# 1-Schematic_Indoor_WiFi_temperature_sens.net
KiCad netlist of a schematic drawn in EasyEDA
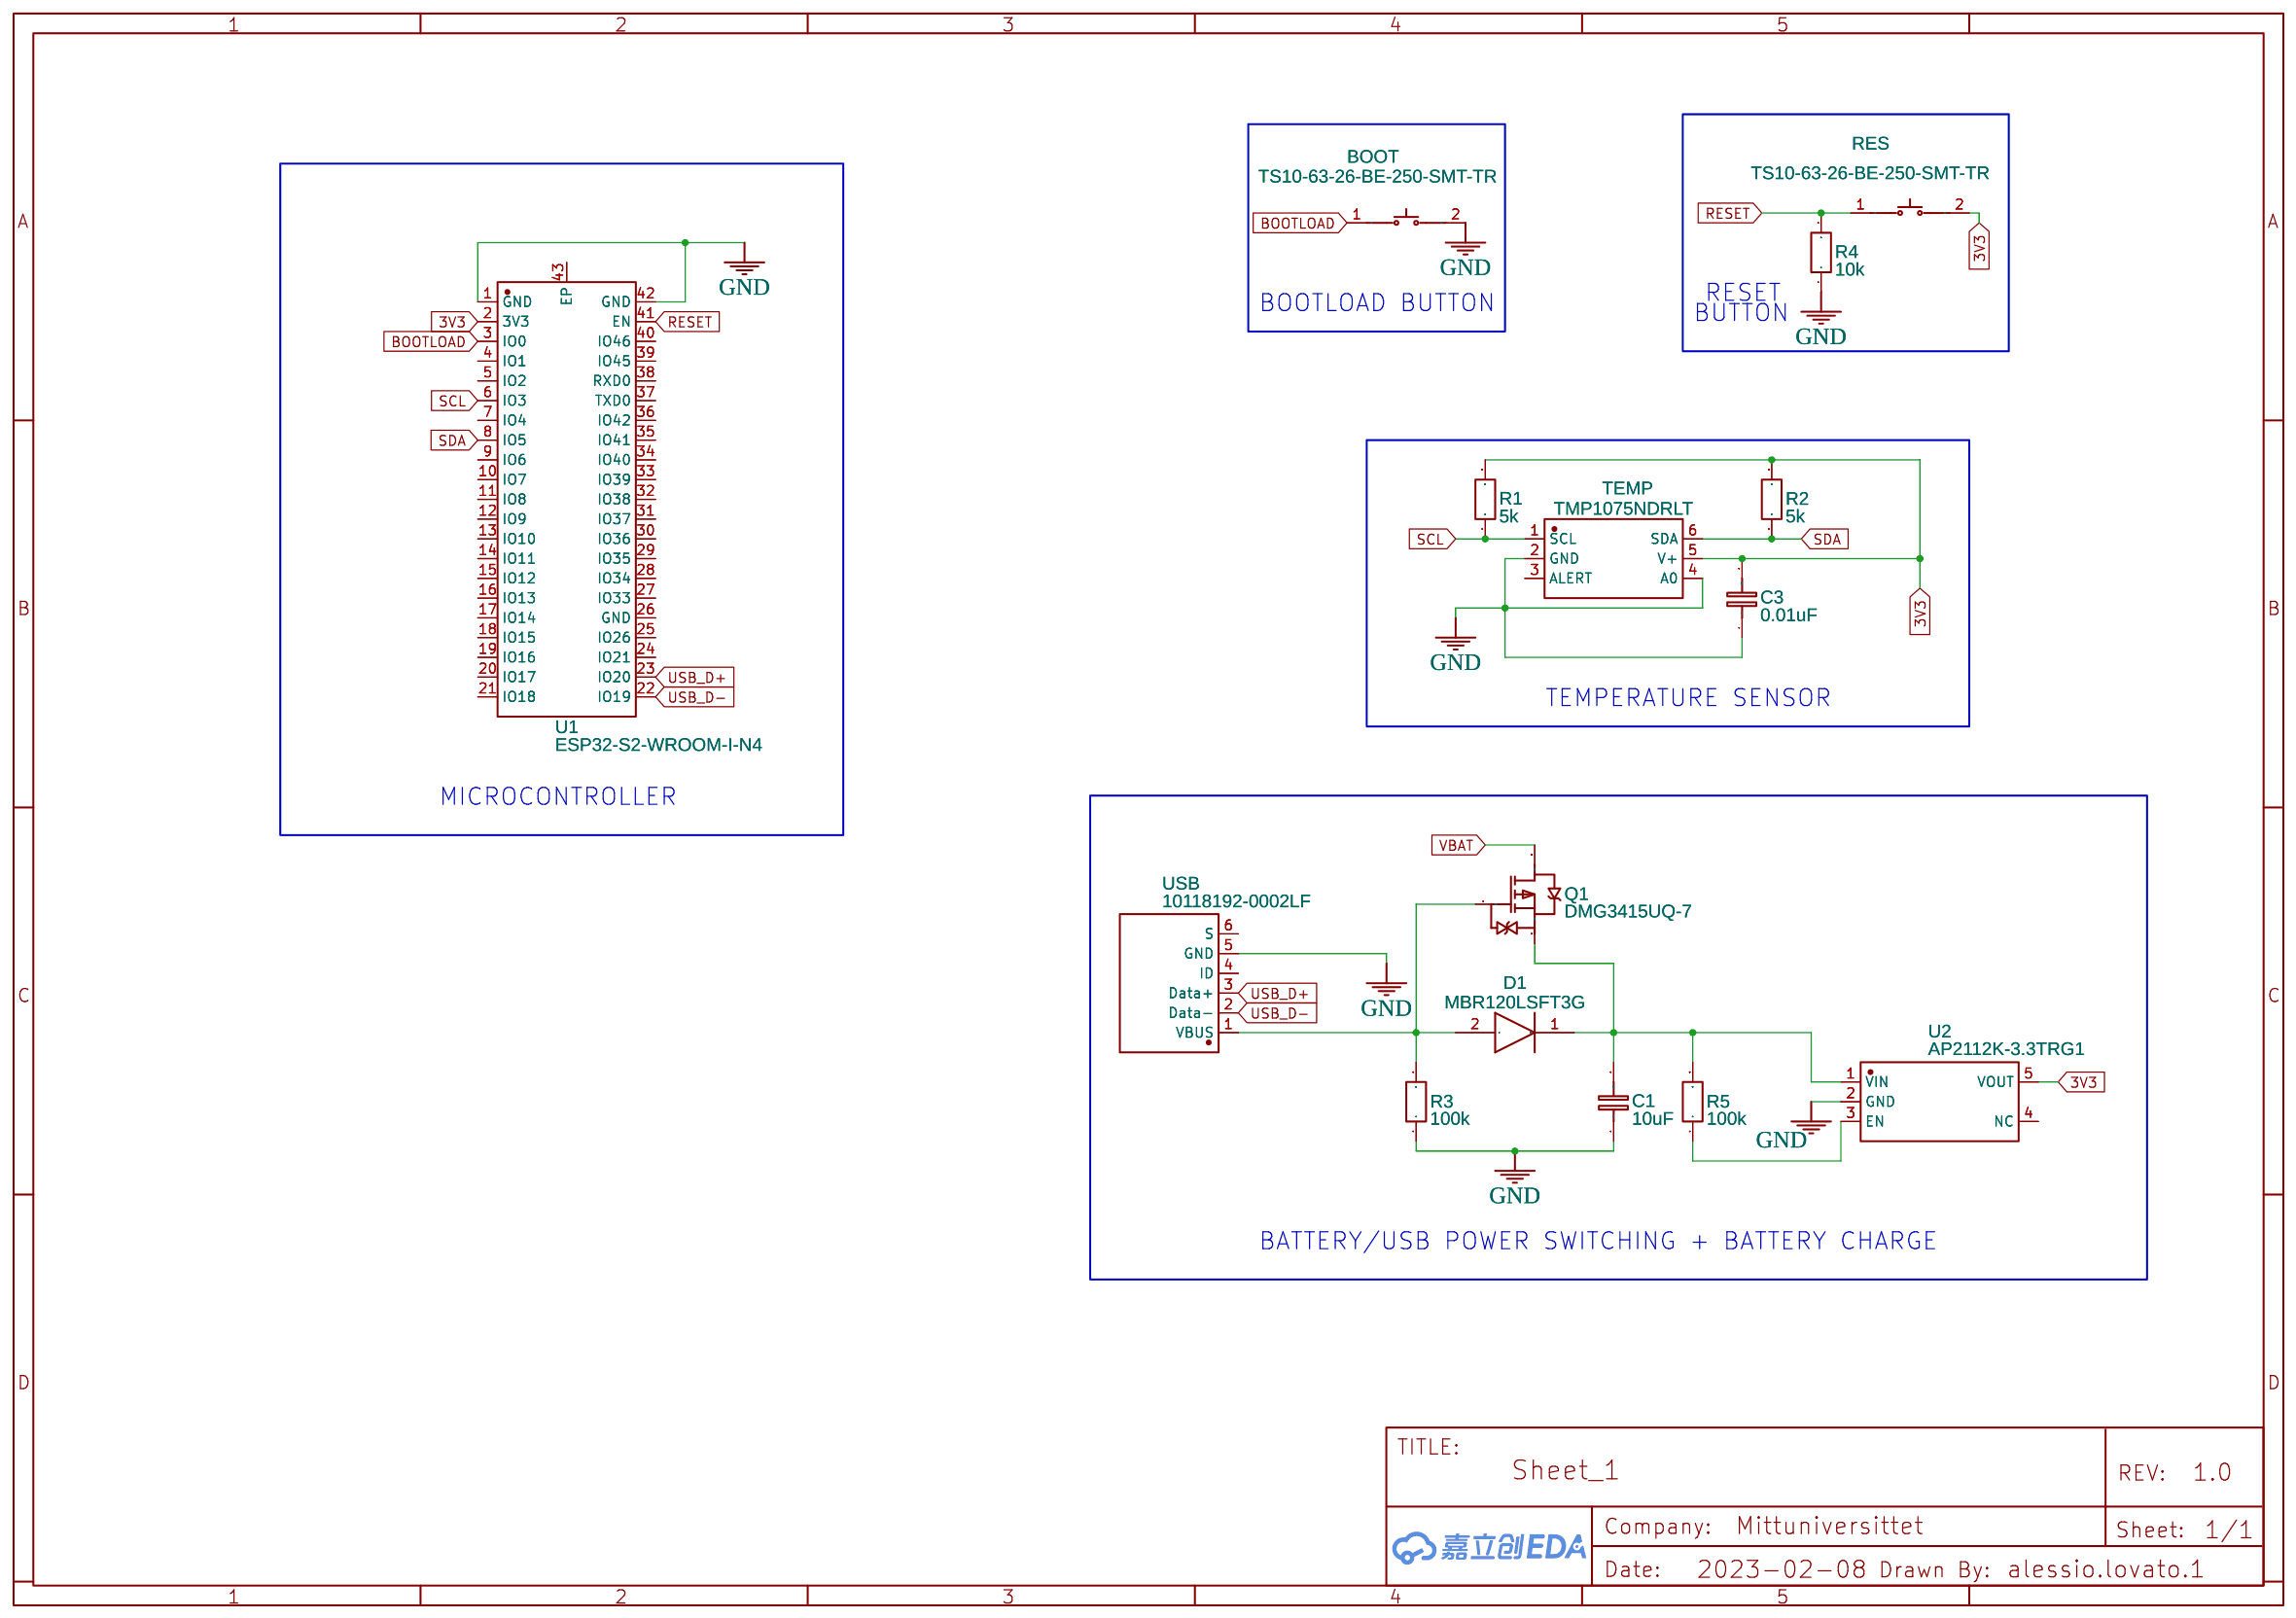
[diagram p0: schematic sheet]

(export (version "E")
  (design (tool "Eeschema 10.0.6"))
  (components
    (comp (ref "BOOT")
      (value "TS10-63-26-BE-250-SMT-TR")
      (fields (field (name "BOM_Supplier Part") "C4364821"))
      (libsource (lib "") (part "TS10-63-26-BE-250-SMT-TR_1"))
    )
    (comp (ref "C1") (value "10uF") (libsource (lib "") (part "C_0603_EU")))
    (comp (ref "C3") (value "0.01uF") (libsource (lib "") (part "C_0603_EU_1")))
    (comp (ref "D1") (value "MBR120LSFT3G") (libsource (lib "") (part "MBR120LSFT3G")))
    (comp (ref "Q1")
      (value "DMG3415UQ-7")
      (fields (field (name "BOM_Supplier Part") "C459537"))
      (libsource (lib "") (part "DMG3415UQ-7"))
    )
    (comp (ref "R1") (value "5k") (libsource (lib "") (part "R_0603_EU")))
    (comp (ref "R2") (value "5k") (libsource (lib "") (part "R_0603_EU")))
    (comp (ref "R3") (value "100k") (libsource (lib "") (part "R_0603_EU")))
    (comp (ref "R4") (value "10k") (libsource (lib "") (part "R_0603_EU")))
    (comp (ref "R5") (value "100k") (libsource (lib "") (part "R_0603_EU")))
    (comp (ref "RES")
      (value "TS10-63-26-BE-250-SMT-TR")
      (fields (field (name "BOM_Supplier Part") "C4364821"))
      (libsource (lib "") (part "TS10-63-26-BE-250-SMT-TR"))
    )
    (comp (ref "TEMP")
      (value "TMP1075NDRLT")
      (fields (field (name "BOM_Supplier Part") "C3663591"))
      (libsource (lib "") (part "TMP1075NDRLT"))
    )
    (comp (ref "U1")
      (value "ESP32-S2-WROOM-I-N4")
      (fields (field (name "BOM_Supplier Part") "C3013911"))
      (libsource (lib "") (part "ESP32-S2-WROOM-I-N4"))
    )
    (comp (ref "U2")
      (value "AP2112K-3.3TRG1")
      (fields (field (name "BOM_Supplier Part") "C51118"))
      (libsource (lib "") (part "AP2112K-3.3TRG1"))
    )
    (comp (ref "USB")
      (value "10118192-0002LF")
      (fields (field (name "BOM_Supplier Part") "C2972784"))
      (libsource (lib "") (part "10118192-0002LF"))
    )
  )
  (nets
    (net (code "1") (name "3V3") (class "Default")
      (node (ref "C3") (pin "2") (pinfunction "2_2") (pintype "unspecified"))
      (node (ref "R1") (pin "2") (pinfunction "2_2") (pintype "unspecified"))
      (node (ref "R2") (pin "2") (pinfunction "2_2") (pintype "unspecified"))
      (node (ref "RES") (pin "2") (pinfunction "2_2") (pintype "unspecified"))
      (node (ref "TEMP") (pin "5") (pinfunction "V+_5") (pintype "unspecified"))
      (node (ref "U1") (pin "2") (pinfunction "3V3_2") (pintype "unspecified"))
      (node (ref "U2") (pin "5") (pinfunction "VOUT_5") (pintype "unspecified"))
    )
    (net (code "2") (name "BOOTLOAD") (class "Default")
      (node (ref "BOOT") (pin "1") (pinfunction "1_1") (pintype "unspecified"))
      (node (ref "U1") (pin "3") (pinfunction "IO0_3") (pintype "unspecified"))
    )
    (net (code "3") (name "GND") (class "Default")
      (node (ref "BOOT") (pin "2") (pinfunction "2_2") (pintype "unspecified"))
      (node (ref "C1") (pin "1") (pinfunction "1_1") (pintype "unspecified"))
      (node (ref "C3") (pin "1") (pinfunction "1_1") (pintype "unspecified"))
      (node (ref "R3") (pin "1") (pinfunction "1_1") (pintype "unspecified"))
      (node (ref "R4") (pin "1") (pinfunction "1_1") (pintype "unspecified"))
      (node (ref "TEMP") (pin "2") (pinfunction "GND_2") (pintype "unspecified"))
      (node (ref "TEMP") (pin "4") (pinfunction "A0_4") (pintype "unspecified"))
      (node (ref "U1") (pin "1") (pinfunction "GND_1") (pintype "unspecified"))
      (node (ref "U1") (pin "42") (pinfunction "GND_42") (pintype "unspecified"))
      (node (ref "U2") (pin "2") (pinfunction "GND_2") (pintype "unspecified"))
      (node (ref "USB") (pin "5") (pinfunction "GND_5") (pintype "unspecified"))
    )
    (net (code "4") (name "Net-(D1-A)") (class "Default")
      (node (ref "D1") (pin "2") (pinfunction "A_2") (pintype "bidirectional"))
      (node (ref "Q1") (pin "1") (pinfunction "G_1") (pintype "unspecified"))
      (node (ref "R3") (pin "2") (pinfunction "2_2") (pintype "unspecified"))
      (node (ref "USB") (pin "1") (pinfunction "VBUS_1") (pintype "unspecified"))
    )
    (net (code "5") (name "Net-(D1-K)") (class "Default")
      (node (ref "C1") (pin "2") (pinfunction "2_2") (pintype "unspecified"))
      (node (ref "D1") (pin "1") (pinfunction "K_1") (pintype "bidirectional"))
      (node (ref "Q1") (pin "2") (pinfunction "S_2") (pintype "unspecified"))
      (node (ref "R5") (pin "2") (pinfunction "2_2") (pintype "unspecified"))
      (node (ref "U2") (pin "1") (pinfunction "VIN_1") (pintype "unspecified"))
    )
    (net (code "6") (name "Net-(U2-EN)") (class "Default")
      (node (ref "R5") (pin "1") (pinfunction "1_1") (pintype "unspecified"))
      (node (ref "U2") (pin "3") (pinfunction "EN_3") (pintype "unspecified"))
    )
    (net (code "7") (name "RESET") (class "Default")
      (node (ref "R4") (pin "2") (pinfunction "2_2") (pintype "unspecified"))
      (node (ref "RES") (pin "1") (pinfunction "1_1") (pintype "unspecified"))
      (node (ref "U1") (pin "41") (pinfunction "EN_41") (pintype "unspecified"))
    )
    (net (code "8") (name "SCL") (class "Default")
      (node (ref "R1") (pin "1") (pinfunction "1_1") (pintype "unspecified"))
      (node (ref "TEMP") (pin "1") (pinfunction "SCL_1") (pintype "unspecified"))
      (node (ref "U1") (pin "6") (pinfunction "IO3_6") (pintype "unspecified"))
    )
    (net (code "9") (name "SDA") (class "Default")
      (node (ref "R2") (pin "1") (pinfunction "1_1") (pintype "unspecified"))
      (node (ref "TEMP") (pin "6") (pinfunction "SDA_6") (pintype "unspecified"))
      (node (ref "U1") (pin "8") (pinfunction "IO5_8") (pintype "unspecified"))
    )
    (net (code "10") (name "USB_D+") (class "Default")
      (node (ref "U1") (pin "23") (pinfunction "IO20_23") (pintype "unspecified"))
      (node (ref "USB") (pin "3") (pinfunction "Data+_3") (pintype "unspecified"))
    )
    (net (code "11") (name "USB_D-") (class "Default")
      (node (ref "U1") (pin "22") (pinfunction "IO19_22") (pintype "unspecified"))
      (node (ref "USB") (pin "2") (pinfunction "Data-_2") (pintype "unspecified"))
    )
    (net (code "12") (name "VBAT") (class "Default")
      (node (ref "Q1") (pin "3") (pinfunction "D_3") (pintype "unspecified"))
    )
    (net (code "13") (name "unconnected-(TEMP-ALERT-Pad3)") (class "Default")
      (node (ref "TEMP") (pin "3") (pinfunction "ALERT_3") (pintype "unspecified"))
    )
    (net (code "14") (name "unconnected-(U1-EP-Pad43)") (class "Default")
      (node (ref "U1") (pin "43") (pinfunction "EP_43") (pintype "unspecified"))
    )
    (net (code "15") (name "unconnected-(U1-GND-Pad26)") (class "Default")
      (node (ref "U1") (pin "26") (pinfunction "GND_26") (pintype "unspecified"))
    )
    (net (code "16") (name "unconnected-(U1-IO1-Pad4)") (class "Default")
      (node (ref "U1") (pin "4") (pinfunction "IO1_4") (pintype "unspecified"))
    )
    (net (code "17") (name "unconnected-(U1-IO2-Pad5)") (class "Default")
      (node (ref "U1") (pin "5") (pinfunction "IO2_5") (pintype "unspecified"))
    )
    (net (code "18") (name "unconnected-(U1-IO4-Pad7)") (class "Default")
      (node (ref "U1") (pin "7") (pinfunction "IO4_7") (pintype "unspecified"))
    )
    (net (code "19") (name "unconnected-(U1-IO6-Pad9)") (class "Default")
      (node (ref "U1") (pin "9") (pinfunction "IO6_9") (pintype "unspecified"))
    )
    (net (code "20") (name "unconnected-(U1-IO7-Pad10)") (class "Default")
      (node (ref "U1") (pin "10") (pinfunction "IO7_10") (pintype "unspecified"))
    )
    (net (code "21") (name "unconnected-(U1-IO8-Pad11)") (class "Default")
      (node (ref "U1") (pin "11") (pinfunction "IO8_11") (pintype "unspecified"))
    )
    (net (code "22") (name "unconnected-(U1-IO9-Pad12)") (class "Default")
      (node (ref "U1") (pin "12") (pinfunction "IO9_12") (pintype "unspecified"))
    )
    (net (code "23") (name "unconnected-(U1-IO10-Pad13)") (class "Default")
      (node (ref "U1") (pin "13") (pinfunction "IO10_13") (pintype "unspecified"))
    )
    (net (code "24") (name "unconnected-(U1-IO11-Pad14)") (class "Default")
      (node (ref "U1") (pin "14") (pinfunction "IO11_14") (pintype "unspecified"))
    )
    (net (code "25") (name "unconnected-(U1-IO12-Pad15)") (class "Default")
      (node (ref "U1") (pin "15") (pinfunction "IO12_15") (pintype "unspecified"))
    )
    (net (code "26") (name "unconnected-(U1-IO13-Pad16)") (class "Default")
      (node (ref "U1") (pin "16") (pinfunction "IO13_16") (pintype "unspecified"))
    )
    (net (code "27") (name "unconnected-(U1-IO14-Pad17)") (class "Default")
      (node (ref "U1") (pin "17") (pinfunction "IO14_17") (pintype "unspecified"))
    )
    (net (code "28") (name "unconnected-(U1-IO15-Pad18)") (class "Default")
      (node (ref "U1") (pin "18") (pinfunction "IO15_18") (pintype "unspecified"))
    )
    (net (code "29") (name "unconnected-(U1-IO16-Pad19)") (class "Default")
      (node (ref "U1") (pin "19") (pinfunction "IO16_19") (pintype "unspecified"))
    )
    (net (code "30") (name "unconnected-(U1-IO17-Pad20)") (class "Default")
      (node (ref "U1") (pin "20") (pinfunction "IO17_20") (pintype "unspecified"))
    )
    (net (code "31") (name "unconnected-(U1-IO18-Pad21)") (class "Default")
      (node (ref "U1") (pin "21") (pinfunction "IO18_21") (pintype "unspecified"))
    )
    (net (code "32") (name "unconnected-(U1-IO21-Pad24)") (class "Default")
      (node (ref "U1") (pin "24") (pinfunction "IO21_24") (pintype "unspecified"))
    )
    (net (code "33") (name "unconnected-(U1-IO26-Pad25)") (class "Default")
      (node (ref "U1") (pin "25") (pinfunction "IO26_25") (pintype "unspecified"))
    )
    (net (code "34") (name "unconnected-(U1-IO33-Pad27)") (class "Default")
      (node (ref "U1") (pin "27") (pinfunction "IO33_27") (pintype "unspecified"))
    )
    (net (code "35") (name "unconnected-(U1-IO34-Pad28)") (class "Default")
      (node (ref "U1") (pin "28") (pinfunction "IO34_28") (pintype "unspecified"))
    )
    (net (code "36") (name "unconnected-(U1-IO35-Pad29)") (class "Default")
      (node (ref "U1") (pin "29") (pinfunction "IO35_29") (pintype "unspecified"))
    )
    (net (code "37") (name "unconnected-(U1-IO36-Pad30)") (class "Default")
      (node (ref "U1") (pin "30") (pinfunction "IO36_30") (pintype "unspecified"))
    )
    (net (code "38") (name "unconnected-(U1-IO37-Pad31)") (class "Default")
      (node (ref "U1") (pin "31") (pinfunction "IO37_31") (pintype "unspecified"))
    )
    (net (code "39") (name "unconnected-(U1-IO38-Pad32)") (class "Default")
      (node (ref "U1") (pin "32") (pinfunction "IO38_32") (pintype "unspecified"))
    )
    (net (code "40") (name "unconnected-(U1-IO39-Pad33)") (class "Default")
      (node (ref "U1") (pin "33") (pinfunction "IO39_33") (pintype "unspecified"))
    )
    (net (code "41") (name "unconnected-(U1-IO40-Pad34)") (class "Default")
      (node (ref "U1") (pin "34") (pinfunction "IO40_34") (pintype "unspecified"))
    )
    (net (code "42") (name "unconnected-(U1-IO41-Pad35)") (class "Default")
      (node (ref "U1") (pin "35") (pinfunction "IO41_35") (pintype "unspecified"))
    )
    (net (code "43") (name "unconnected-(U1-IO42-Pad36)") (class "Default")
      (node (ref "U1") (pin "36") (pinfunction "IO42_36") (pintype "unspecified"))
    )
    (net (code "44") (name "unconnected-(U1-IO45-Pad39)") (class "Default")
      (node (ref "U1") (pin "39") (pinfunction "IO45_39") (pintype "unspecified"))
    )
    (net (code "45") (name "unconnected-(U1-IO46-Pad40)") (class "Default")
      (node (ref "U1") (pin "40") (pinfunction "IO46_40") (pintype "unspecified"))
    )
    (net (code "46") (name "unconnected-(U1-RXD0-Pad38)") (class "Default")
      (node (ref "U1") (pin "38") (pinfunction "RXD0_38") (pintype "unspecified"))
    )
    (net (code "47") (name "unconnected-(U1-TXD0-Pad37)") (class "Default")
      (node (ref "U1") (pin "37") (pinfunction "TXD0_37") (pintype "unspecified"))
    )
    (net (code "48") (name "unconnected-(U2-NC-Pad4)") (class "Default")
      (node (ref "U2") (pin "4") (pinfunction "NC_4") (pintype "unspecified"))
    )
    (net (code "49") (name "unconnected-(USB-ID-Pad4)") (class "Default")
      (node (ref "USB") (pin "4") (pinfunction "ID_4") (pintype "unspecified"))
    )
    (net (code "50") (name "unconnected-(USB-S-Pad6)") (class "Default")
      (node (ref "USB") (pin "6") (pinfunction "S_6") (pintype "unspecified"))
    )
  )
)
